# Relay.net
KiCad netlist of a schematic drawn in Altium Designer
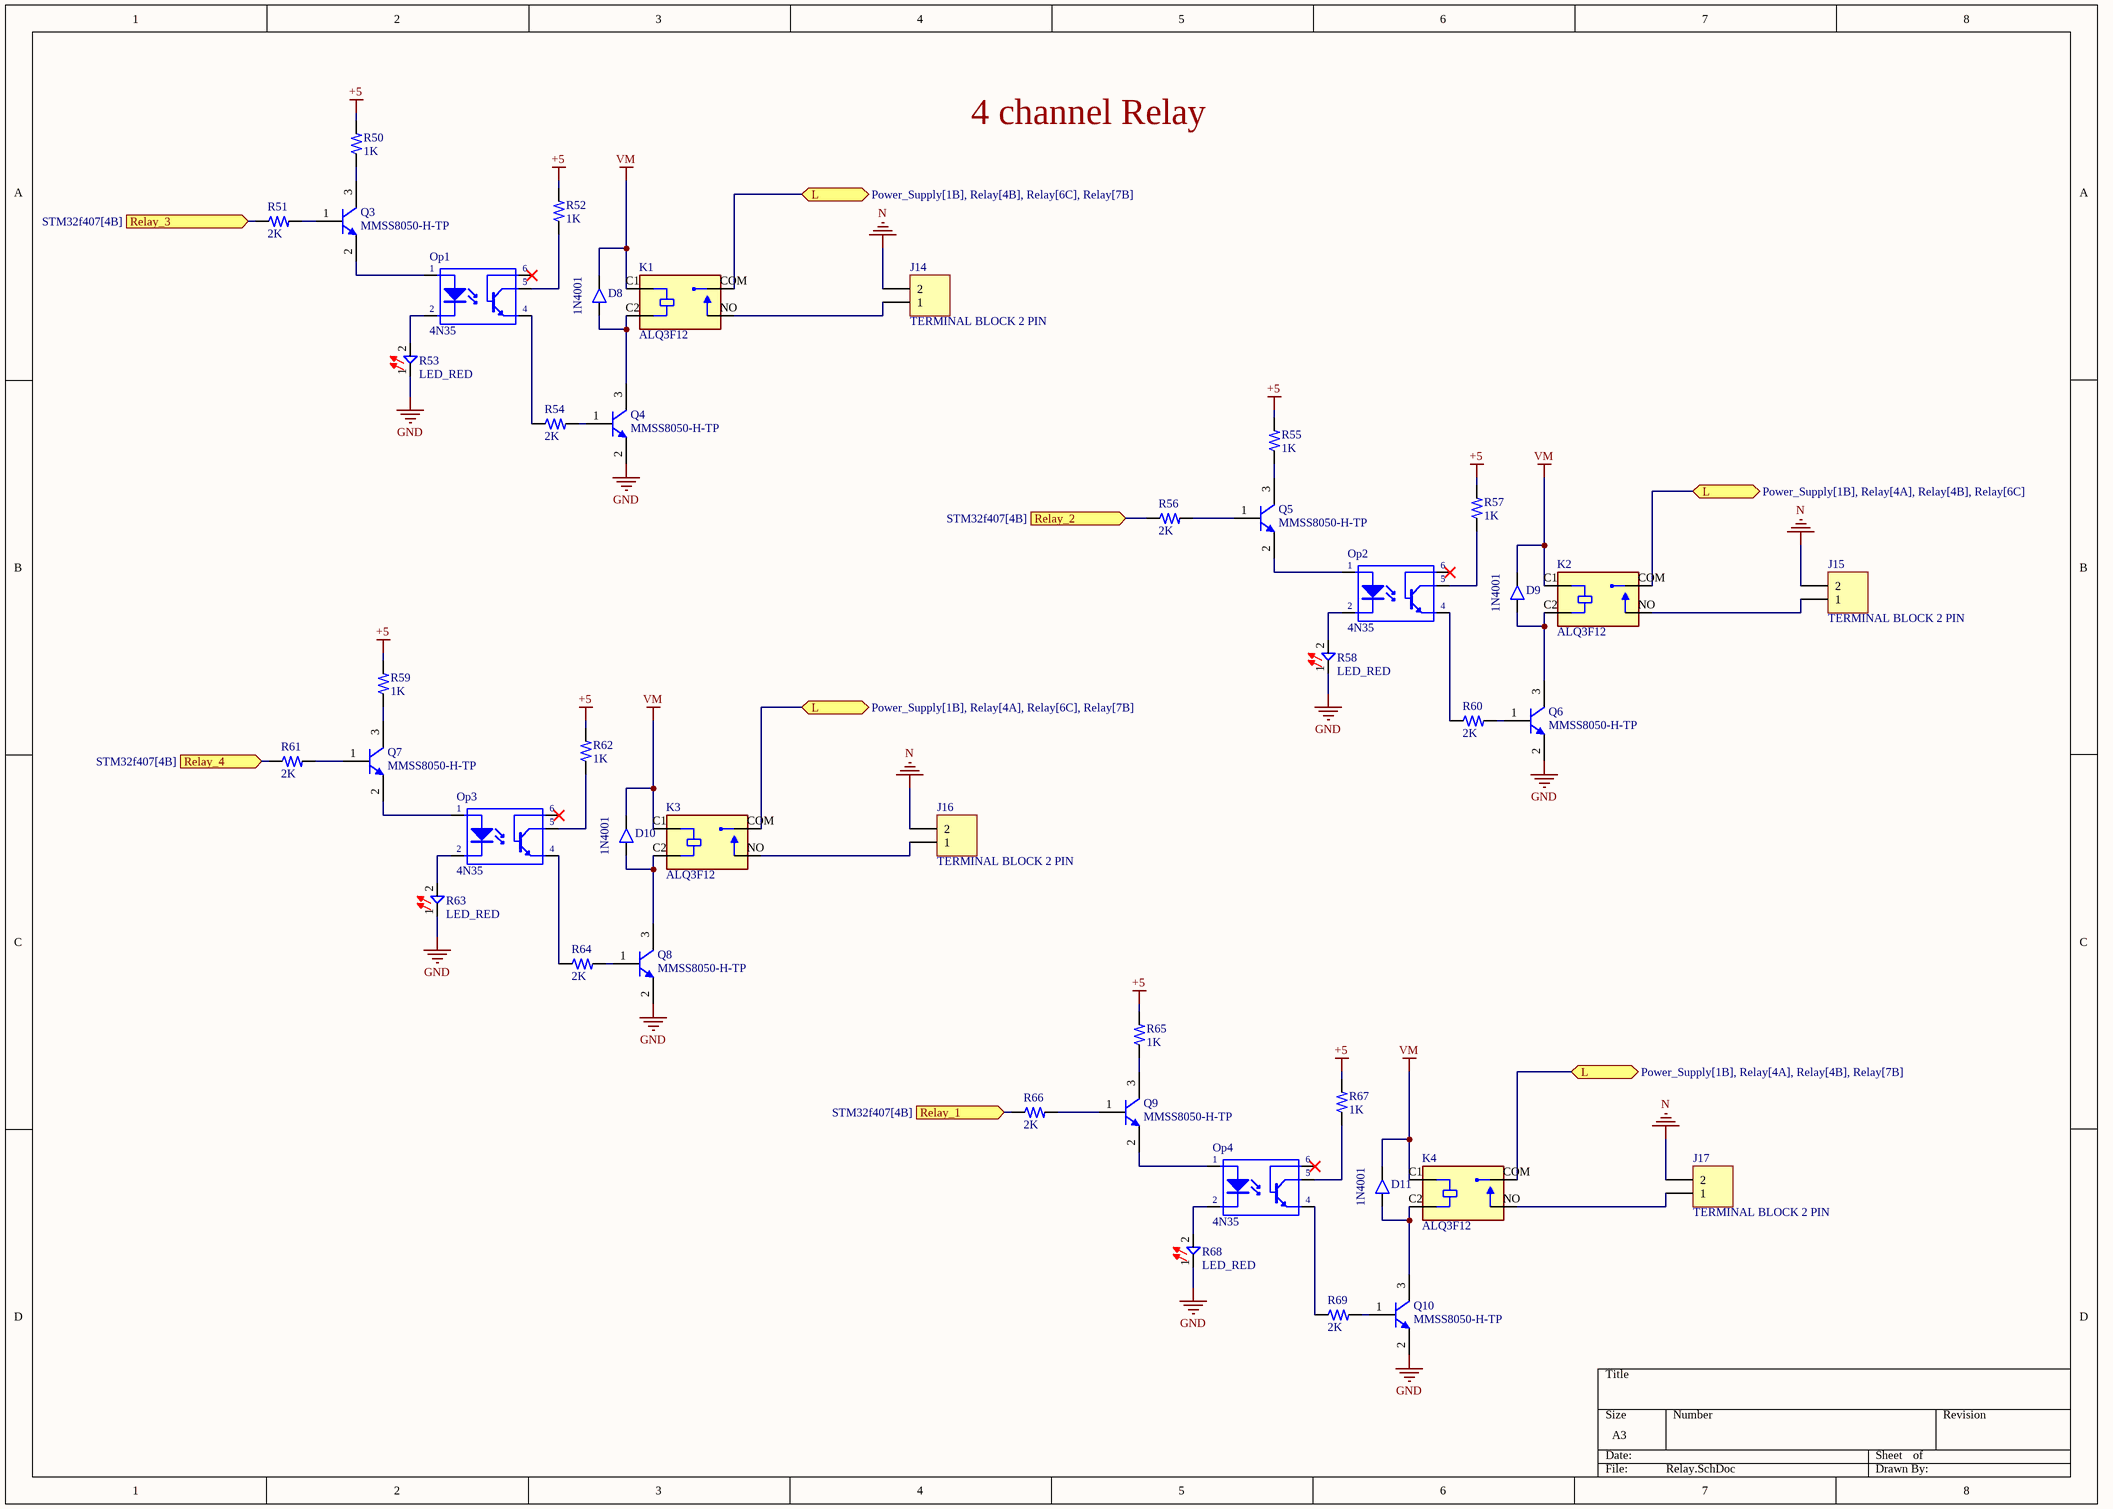
[diagram p0: Relay.SchDoc]

(export (version "E")
  (design (tool "Eeschema 10.0.6"))
  (components
    (comp (ref "D8")
      (value "1N4001")
      (footprint "1N4001")
      (description "1N4001 Series 1 A 50 V Axial Lead Standard Recovery Rectifier - CASE 59-10")
      (fields
        (field (name "MANUFACTURER") "ON Semiconductor")
        (field (name "MANUFACTURER PART NUMBER") "1N4001RLG")
      )
      (libsource (lib "Schematics_Library_Hanif") (part "Diode_1N4001RLG"))
    )
    (comp (ref "D9")
      (value "1N4001")
      (footprint "1N4001")
      (description "1N4001 Series 1 A 50 V Axial Lead Standard Recovery Rectifier - CASE 59-10")
      (fields
        (field (name "MANUFACTURER") "ON Semiconductor")
        (field (name "MANUFACTURER PART NUMBER") "1N4001RLG")
      )
      (libsource (lib "Schematics_Library_Hanif") (part "Diode_1N4001RLG"))
    )
    (comp (ref "D10")
      (value "1N4001")
      (footprint "1N4001")
      (description "1N4001 Series 1 A 50 V Axial Lead Standard Recovery Rectifier - CASE 59-10")
      (fields
        (field (name "MANUFACTURER") "ON Semiconductor")
        (field (name "MANUFACTURER PART NUMBER") "1N4001RLG")
      )
      (libsource (lib "Schematics_Library_Hanif") (part "Diode_1N4001RLG"))
    )
    (comp (ref "D11")
      (value "1N4001")
      (footprint "1N4001")
      (description "1N4001 Series 1 A 50 V Axial Lead Standard Recovery Rectifier - CASE 59-10")
      (fields
        (field (name "MANUFACTURER") "ON Semiconductor")
        (field (name "MANUFACTURER PART NUMBER") "1N4001RLG")
      )
      (libsource (lib "Schematics_Library_Hanif") (part "Diode_1N4001RLG"))
    )
    (comp (ref "J14")
      (value "TERMINAL BLOCK 2 PIN")
      (footprint "CON2_P196_1729128_TH_ST")
      (description "2 Pins, 1 Row 5mm Pitch, straight Connector, male")
      (fields
        (field (name "MANUFACTURER") "Phoenix Contact")
        (field (name "MANUFACTURER PART NUMBER") "MKDSN1,5/2")
      )
      (libsource (lib "Schematics_Library_Hanif") (part "CON-TB_2X1-196-ST-TH"))
    )
    (comp (ref "J15")
      (value "TERMINAL BLOCK 2 PIN")
      (footprint "CON2_P196_1729128_TH_ST")
      (description "2 Pins, 1 Row 5mm Pitch, straight Connector, male")
      (fields
        (field (name "MANUFACTURER") "Phoenix Contact")
        (field (name "MANUFACTURER PART NUMBER") "MKDSN1,5/2")
      )
      (libsource (lib "Schematics_Library_Hanif") (part "CON-TB_2X1-196-ST-TH"))
    )
    (comp (ref "J16")
      (value "TERMINAL BLOCK 2 PIN")
      (footprint "CON2_P196_1729128_TH_ST")
      (description "2 Pins, 1 Row 5mm Pitch, straight Connector, male")
      (fields
        (field (name "MANUFACTURER") "Phoenix Contact")
        (field (name "MANUFACTURER PART NUMBER") "MKDSN1,5/2")
      )
      (libsource (lib "Schematics_Library_Hanif") (part "CON-TB_2X1-196-ST-TH"))
    )
    (comp (ref "J17")
      (value "TERMINAL BLOCK 2 PIN")
      (footprint "CON2_P196_1729128_TH_ST")
      (description "2 Pins, 1 Row 5mm Pitch, straight Connector, male")
      (fields
        (field (name "MANUFACTURER") "Phoenix Contact")
        (field (name "MANUFACTURER PART NUMBER") "MKDSN1,5/2")
      )
      (libsource (lib "Schematics_Library_Hanif") (part "CON-TB_2X1-196-ST-TH"))
    )
    (comp (ref "K1")
      (value "ALQ3F12")
      (footprint "Relay_ALQ3F12")
      (description "RELAY GEN PURPOSE SPST 10A 12V")
      (fields (field (name "MANUFACTURER") "Panasonic"))
      (libsource (lib "Schematics_Library_Hanif") (part "Relay_12V_10A"))
    )
    (comp (ref "K2")
      (value "ALQ3F12")
      (footprint "Relay_ALQ3F12")
      (description "RELAY GEN PURPOSE SPST 10A 12V")
      (fields (field (name "MANUFACTURER") "Panasonic"))
      (libsource (lib "Schematics_Library_Hanif") (part "Relay_12V_10A"))
    )
    (comp (ref "K3")
      (value "ALQ3F12")
      (footprint "Relay_ALQ3F12")
      (description "RELAY GEN PURPOSE SPST 10A 12V")
      (fields (field (name "MANUFACTURER") "Panasonic"))
      (libsource (lib "Schematics_Library_Hanif") (part "Relay_12V_10A"))
    )
    (comp (ref "K4")
      (value "ALQ3F12")
      (footprint "Relay_ALQ3F12")
      (description "RELAY GEN PURPOSE SPST 10A 12V")
      (fields (field (name "MANUFACTURER") "Panasonic"))
      (libsource (lib "Schematics_Library_Hanif") (part "Relay_12V_10A"))
    )
    (comp (ref "Op1")
      (value "4N35")
      (footprint "DIP6_100_300_78X45_TH")
      (description "Power Field-Effect Transistor, 14.5A, 30V, 0.0055ohm, 1-Element, N-Channel, MOSFET")
      (fields
        (field (name "MANUFACTURER") "ON Semiconductor")
        (field (name "MANUFACTURER PART NUMBER") "NTD4804N-35G")
      )
      (libsource (lib "Schematics_Library_Hanif") (part "OPTO_1CH-5KV-50mA-DIP6"))
    )
    (comp (ref "Op2")
      (value "4N35")
      (footprint "DIP6_100_300_78X45_TH")
      (description "Power Field-Effect Transistor, 14.5A, 30V, 0.0055ohm, 1-Element, N-Channel, MOSFET")
      (fields
        (field (name "MANUFACTURER") "ON Semiconductor")
        (field (name "MANUFACTURER PART NUMBER") "NTD4804N-35G")
      )
      (libsource (lib "Schematics_Library_Hanif") (part "OPTO_1CH-5KV-50mA-DIP6"))
    )
    (comp (ref "Op3")
      (value "4N35")
      (footprint "DIP6_100_300_78X45_TH")
      (description "Power Field-Effect Transistor, 14.5A, 30V, 0.0055ohm, 1-Element, N-Channel, MOSFET")
      (fields
        (field (name "MANUFACTURER") "ON Semiconductor")
        (field (name "MANUFACTURER PART NUMBER") "NTD4804N-35G")
      )
      (libsource (lib "Schematics_Library_Hanif") (part "OPTO_1CH-5KV-50mA-DIP6"))
    )
    (comp (ref "Op4")
      (value "4N35")
      (footprint "DIP6_100_300_78X45_TH")
      (description "Power Field-Effect Transistor, 14.5A, 30V, 0.0055ohm, 1-Element, N-Channel, MOSFET")
      (fields
        (field (name "MANUFACTURER") "ON Semiconductor")
        (field (name "MANUFACTURER PART NUMBER") "NTD4804N-35G")
      )
      (libsource (lib "Schematics_Library_Hanif") (part "OPTO_1CH-5KV-50mA-DIP6"))
    )
    (comp (ref "Q3")
      (value "MMSS8050-H-TP")
      (footprint "SOT_23_3")
      (description "Bipolar (BJT) Transistor NPN 25V 1.5A 100MHz 625mW Surface Mount SOT-23")
      (fields (field (name "MANUFACTURER") "MCC"))
      (libsource (lib "Schematics_Library_Hanif") (part "TRNS-NPN_25V-1.5A-SOT23"))
    )
    (comp (ref "Q4")
      (value "MMSS8050-H-TP")
      (footprint "SOT_23_3")
      (description "Bipolar (BJT) Transistor NPN 25V 1.5A 100MHz 625mW Surface Mount SOT-23")
      (fields (field (name "MANUFACTURER") "MCC"))
      (libsource (lib "Schematics_Library_Hanif") (part "TRNS-NPN_25V-1.5A-SOT23"))
    )
    (comp (ref "Q5")
      (value "MMSS8050-H-TP")
      (footprint "SOT_23_3")
      (description "Bipolar (BJT) Transistor NPN 25V 1.5A 100MHz 625mW Surface Mount SOT-23")
      (fields (field (name "MANUFACTURER") "MCC"))
      (libsource (lib "Schematics_Library_Hanif") (part "TRNS-NPN_25V-1.5A-SOT23"))
    )
    (comp (ref "Q6")
      (value "MMSS8050-H-TP")
      (footprint "SOT_23_3")
      (description "Bipolar (BJT) Transistor NPN 25V 1.5A 100MHz 625mW Surface Mount SOT-23")
      (fields (field (name "MANUFACTURER") "MCC"))
      (libsource (lib "Schematics_Library_Hanif") (part "TRNS-NPN_25V-1.5A-SOT23"))
    )
    (comp (ref "Q7")
      (value "MMSS8050-H-TP")
      (footprint "SOT_23_3")
      (description "Bipolar (BJT) Transistor NPN 25V 1.5A 100MHz 625mW Surface Mount SOT-23")
      (fields (field (name "MANUFACTURER") "MCC"))
      (libsource (lib "Schematics_Library_Hanif") (part "TRNS-NPN_25V-1.5A-SOT23"))
    )
    (comp (ref "Q8")
      (value "MMSS8050-H-TP")
      (footprint "SOT_23_3")
      (description "Bipolar (BJT) Transistor NPN 25V 1.5A 100MHz 625mW Surface Mount SOT-23")
      (fields (field (name "MANUFACTURER") "MCC"))
      (libsource (lib "Schematics_Library_Hanif") (part "TRNS-NPN_25V-1.5A-SOT23"))
    )
    (comp (ref "Q9")
      (value "MMSS8050-H-TP")
      (footprint "SOT_23_3")
      (description "Bipolar (BJT) Transistor NPN 25V 1.5A 100MHz 625mW Surface Mount SOT-23")
      (fields (field (name "MANUFACTURER") "MCC"))
      (libsource (lib "Schematics_Library_Hanif") (part "TRNS-NPN_25V-1.5A-SOT23"))
    )
    (comp (ref "Q10")
      (value "MMSS8050-H-TP")
      (footprint "SOT_23_3")
      (description "Bipolar (BJT) Transistor NPN 25V 1.5A 100MHz 625mW Surface Mount SOT-23")
      (fields (field (name "MANUFACTURER") "MCC"))
      (libsource (lib "Schematics_Library_Hanif") (part "TRNS-NPN_25V-1.5A-SOT23"))
    )
    (comp (ref "R50")
      (value "1K")
      (footprint "Resistor_0603")
      (description "Res Thick Film 0603 1K Ohm 1% 0.1W(1/10W) ±100ppm/C Pad SMD T/R")
      (fields
        (field (name "MANUFACTURER") "Walsin Technologies")
        (field (name "MANUFACTURER PART NUMBER") "WR06X1001FTL")
      )
      (libsource (lib "Schematics_Library_Hanif") (part "R_1k_0603"))
    )
    (comp (ref "R51")
      (value "2K")
      (footprint "Resistor_0603")
      (description "Res Thin Film 0603 2K Ohm 1% 0.125W(1/8W) ±100ppm/C Sulfur Resistant Pad SMD T/R")
      (fields
        (field (name "MANUFACTURER") "Stackpole Electronics")
        (field (name "MANUFACTURER PART NUMBER") "RNCP0603FTD2K00")
      )
      (libsource (lib "Schematics_Library_Hanif") (part "R_2k_0603"))
    )
    (comp (ref "R52")
      (value "1K")
      (footprint "Resistor_0603")
      (description "Res Thick Film 0603 1K Ohm 1% 0.1W(1/10W) ±100ppm/C Pad SMD T/R")
      (fields
        (field (name "MANUFACTURER") "Walsin Technologies")
        (field (name "MANUFACTURER PART NUMBER") "WR06X1001FTL")
      )
      (libsource (lib "Schematics_Library_Hanif") (part "R_1k_0603"))
    )
    (comp (ref "R53")
      (value "LED_RED")
      (footprint "LTST-C171KRKT")
      (fields
        (field (name "MANUFACTURER") "Vishay Lite-On")
        (field (name "MANUFACTURER PART NUMBER") "LTST-C171KRKT")
      )
      (libsource (lib "Schematics_Library_Hanif") (part "LED_RED_SMD"))
    )
    (comp (ref "R54")
      (value "2K")
      (footprint "Resistor_0603")
      (description "Res Thin Film 0603 2K Ohm 1% 0.125W(1/8W) ±100ppm/C Sulfur Resistant Pad SMD T/R")
      (fields
        (field (name "MANUFACTURER") "Stackpole Electronics")
        (field (name "MANUFACTURER PART NUMBER") "RNCP0603FTD2K00")
      )
      (libsource (lib "Schematics_Library_Hanif") (part "R_2k_0603"))
    )
    (comp (ref "R55")
      (value "1K")
      (footprint "Resistor_0603")
      (description "Res Thick Film 0603 1K Ohm 1% 0.1W(1/10W) ±100ppm/C Pad SMD T/R")
      (fields
        (field (name "MANUFACTURER") "Walsin Technologies")
        (field (name "MANUFACTURER PART NUMBER") "WR06X1001FTL")
      )
      (libsource (lib "Schematics_Library_Hanif") (part "R_1k_0603"))
    )
    (comp (ref "R56")
      (value "2K")
      (footprint "Resistor_0603")
      (description "Res Thin Film 0603 2K Ohm 1% 0.125W(1/8W) ±100ppm/C Sulfur Resistant Pad SMD T/R")
      (fields
        (field (name "MANUFACTURER") "Stackpole Electronics")
        (field (name "MANUFACTURER PART NUMBER") "RNCP0603FTD2K00")
      )
      (libsource (lib "Schematics_Library_Hanif") (part "R_2k_0603"))
    )
    (comp (ref "R57")
      (value "1K")
      (footprint "Resistor_0603")
      (description "Res Thick Film 0603 1K Ohm 1% 0.1W(1/10W) ±100ppm/C Pad SMD T/R")
      (fields
        (field (name "MANUFACTURER") "Walsin Technologies")
        (field (name "MANUFACTURER PART NUMBER") "WR06X1001FTL")
      )
      (libsource (lib "Schematics_Library_Hanif") (part "R_1k_0603"))
    )
    (comp (ref "R58")
      (value "LED_RED")
      (footprint "LTST-C171KRKT")
      (fields
        (field (name "MANUFACTURER") "Vishay Lite-On")
        (field (name "MANUFACTURER PART NUMBER") "LTST-C171KRKT")
      )
      (libsource (lib "Schematics_Library_Hanif") (part "LED_RED_SMD"))
    )
    (comp (ref "R59")
      (value "1K")
      (footprint "Resistor_0603")
      (description "Res Thick Film 0603 1K Ohm 1% 0.1W(1/10W) ±100ppm/C Pad SMD T/R")
      (fields
        (field (name "MANUFACTURER") "Walsin Technologies")
        (field (name "MANUFACTURER PART NUMBER") "WR06X1001FTL")
      )
      (libsource (lib "Schematics_Library_Hanif") (part "R_1k_0603"))
    )
    (comp (ref "R60")
      (value "2K")
      (footprint "Resistor_0603")
      (description "Res Thin Film 0603 2K Ohm 1% 0.125W(1/8W) ±100ppm/C Sulfur Resistant Pad SMD T/R")
      (fields
        (field (name "MANUFACTURER") "Stackpole Electronics")
        (field (name "MANUFACTURER PART NUMBER") "RNCP0603FTD2K00")
      )
      (libsource (lib "Schematics_Library_Hanif") (part "R_2k_0603"))
    )
    (comp (ref "R61")
      (value "2K")
      (footprint "Resistor_0603")
      (description "Res Thin Film 0603 2K Ohm 1% 0.125W(1/8W) ±100ppm/C Sulfur Resistant Pad SMD T/R")
      (fields
        (field (name "MANUFACTURER") "Stackpole Electronics")
        (field (name "MANUFACTURER PART NUMBER") "RNCP0603FTD2K00")
      )
      (libsource (lib "Schematics_Library_Hanif") (part "R_2k_0603"))
    )
    (comp (ref "R62")
      (value "1K")
      (footprint "Resistor_0603")
      (description "Res Thick Film 0603 1K Ohm 1% 0.1W(1/10W) ±100ppm/C Pad SMD T/R")
      (fields
        (field (name "MANUFACTURER") "Walsin Technologies")
        (field (name "MANUFACTURER PART NUMBER") "WR06X1001FTL")
      )
      (libsource (lib "Schematics_Library_Hanif") (part "R_1k_0603"))
    )
    (comp (ref "R63")
      (value "LED_RED")
      (footprint "LTST-C171KRKT")
      (fields
        (field (name "MANUFACTURER") "Vishay Lite-On")
        (field (name "MANUFACTURER PART NUMBER") "LTST-C171KRKT")
      )
      (libsource (lib "Schematics_Library_Hanif") (part "LED_RED_SMD"))
    )
    (comp (ref "R64")
      (value "2K")
      (footprint "Resistor_0603")
      (description "Res Thin Film 0603 2K Ohm 1% 0.125W(1/8W) ±100ppm/C Sulfur Resistant Pad SMD T/R")
      (fields
        (field (name "MANUFACTURER") "Stackpole Electronics")
        (field (name "MANUFACTURER PART NUMBER") "RNCP0603FTD2K00")
      )
      (libsource (lib "Schematics_Library_Hanif") (part "R_2k_0603"))
    )
    (comp (ref "R65")
      (value "1K")
      (footprint "Resistor_0603")
      (description "Res Thick Film 0603 1K Ohm 1% 0.1W(1/10W) ±100ppm/C Pad SMD T/R")
      (fields
        (field (name "MANUFACTURER") "Walsin Technologies")
        (field (name "MANUFACTURER PART NUMBER") "WR06X1001FTL")
      )
      (libsource (lib "Schematics_Library_Hanif") (part "R_1k_0603"))
    )
    (comp (ref "R66")
      (value "2K")
      (footprint "Resistor_0603")
      (description "Res Thin Film 0603 2K Ohm 1% 0.125W(1/8W) ±100ppm/C Sulfur Resistant Pad SMD T/R")
      (fields
        (field (name "MANUFACTURER") "Stackpole Electronics")
        (field (name "MANUFACTURER PART NUMBER") "RNCP0603FTD2K00")
      )
      (libsource (lib "Schematics_Library_Hanif") (part "R_2k_0603"))
    )
    (comp (ref "R67")
      (value "1K")
      (footprint "Resistor_0603")
      (description "Res Thick Film 0603 1K Ohm 1% 0.1W(1/10W) ±100ppm/C Pad SMD T/R")
      (fields
        (field (name "MANUFACTURER") "Walsin Technologies")
        (field (name "MANUFACTURER PART NUMBER") "WR06X1001FTL")
      )
      (libsource (lib "Schematics_Library_Hanif") (part "R_1k_0603"))
    )
    (comp (ref "R68")
      (value "LED_RED")
      (footprint "LTST-C171KRKT")
      (fields
        (field (name "MANUFACTURER") "Vishay Lite-On")
        (field (name "MANUFACTURER PART NUMBER") "LTST-C171KRKT")
      )
      (libsource (lib "Schematics_Library_Hanif") (part "LED_RED_SMD"))
    )
    (comp (ref "R69")
      (value "2K")
      (footprint "Resistor_0603")
      (description "Res Thin Film 0603 2K Ohm 1% 0.125W(1/8W) ±100ppm/C Sulfur Resistant Pad SMD T/R")
      (fields
        (field (name "MANUFACTURER") "Stackpole Electronics")
        (field (name "MANUFACTURER PART NUMBER") "RNCP0603FTD2K00")
      )
      (libsource (lib "Schematics_Library_Hanif") (part "R_2k_0603"))
    )
  )
  (nets
    (net (code "1") (name "+5") (class "Default")
      (node (ref "R50") (pin "2") (pinfunction "2_2") (pintype "passive"))
      (node (ref "R52") (pin "2") (pinfunction "2_2") (pintype "passive"))
      (node (ref "R55") (pin "2") (pinfunction "2_2") (pintype "passive"))
      (node (ref "R57") (pin "2") (pinfunction "2_2") (pintype "passive"))
      (node (ref "R59") (pin "2") (pinfunction "2_2") (pintype "passive"))
      (node (ref "R62") (pin "2") (pinfunction "2_2") (pintype "passive"))
      (node (ref "R65") (pin "2") (pinfunction "2_2") (pintype "passive"))
      (node (ref "R67") (pin "2") (pinfunction "2_2") (pintype "passive"))
    )
    (net (code "2") (name "/L") (class "Default")
      (node (ref "K1") (pin "COM") (pinfunction "COM_COM") (pintype "passive"))
      (node (ref "K2") (pin "COM") (pinfunction "COM_COM") (pintype "passive"))
      (node (ref "K3") (pin "COM") (pinfunction "COM_COM") (pintype "passive"))
      (node (ref "K4") (pin "COM") (pinfunction "COM_COM") (pintype "passive"))
    )
    (net (code "3") (name "/Relay_1") (class "Default")
      (node (ref "R66") (pin "1") (pinfunction "1_1") (pintype "passive"))
    )
    (net (code "4") (name "/Relay_2") (class "Default")
      (node (ref "R56") (pin "1") (pinfunction "1_1") (pintype "passive"))
    )
    (net (code "5") (name "/Relay_3") (class "Default")
      (node (ref "R51") (pin "1") (pinfunction "1_1") (pintype "passive"))
    )
    (net (code "6") (name "/Relay_4") (class "Default")
      (node (ref "R61") (pin "1") (pinfunction "1_1") (pintype "passive"))
    )
    (net (code "7") (name "GND") (class "Default")
      (node (ref "Q10") (pin "2") (pinfunction "E_2") (pintype "passive"))
      (node (ref "Q4") (pin "2") (pinfunction "E_2") (pintype "passive"))
      (node (ref "Q6") (pin "2") (pinfunction "E_2") (pintype "passive"))
      (node (ref "Q8") (pin "2") (pinfunction "E_2") (pintype "passive"))
      (node (ref "R53") (pin "1") (pinfunction "1_1") (pintype "passive"))
      (node (ref "R58") (pin "1") (pinfunction "1_1") (pintype "passive"))
      (node (ref "R63") (pin "1") (pinfunction "1_1") (pintype "passive"))
      (node (ref "R68") (pin "1") (pinfunction "1_1") (pintype "passive"))
    )
    (net (code "8") (name "N") (class "Default")
      (node (ref "J14") (pin "2") (pinfunction "2_2") (pintype "passive"))
      (node (ref "J15") (pin "2") (pinfunction "2_2") (pintype "passive"))
      (node (ref "J16") (pin "2") (pinfunction "2_2") (pintype "passive"))
      (node (ref "J17") (pin "2") (pinfunction "2_2") (pintype "passive"))
    )
    (net (code "9") (name "Net-(D8-ANODE)") (class "Default")
      (node (ref "D8") (pin "A") (pinfunction "ANODE_A") (pintype "passive"))
      (node (ref "K1") (pin "C2") (pinfunction "COIL2_C2") (pintype "passive"))
      (node (ref "Q4") (pin "3") (pinfunction "C_3") (pintype "passive"))
    )
    (net (code "10") (name "Net-(D9-ANODE)") (class "Default")
      (node (ref "D9") (pin "A") (pinfunction "ANODE_A") (pintype "passive"))
      (node (ref "K2") (pin "C2") (pinfunction "COIL2_C2") (pintype "passive"))
      (node (ref "Q6") (pin "3") (pinfunction "C_3") (pintype "passive"))
    )
    (net (code "11") (name "Net-(D10-ANODE)") (class "Default")
      (node (ref "D10") (pin "A") (pinfunction "ANODE_A") (pintype "passive"))
      (node (ref "K3") (pin "C2") (pinfunction "COIL2_C2") (pintype "passive"))
      (node (ref "Q8") (pin "3") (pinfunction "C_3") (pintype "passive"))
    )
    (net (code "12") (name "Net-(D11-ANODE)") (class "Default")
      (node (ref "D11") (pin "A") (pinfunction "ANODE_A") (pintype "passive"))
      (node (ref "K4") (pin "C2") (pinfunction "COIL2_C2") (pintype "passive"))
      (node (ref "Q10") (pin "3") (pinfunction "C_3") (pintype "passive"))
    )
    (net (code "13") (name "Net-(J14-Pad1)") (class "Default")
      (node (ref "J14") (pin "1") (pinfunction "1_1") (pintype "passive"))
      (node (ref "K1") (pin "NO") (pinfunction "NO_NO") (pintype "passive"))
    )
    (net (code "14") (name "Net-(J15-Pad1)") (class "Default")
      (node (ref "J15") (pin "1") (pinfunction "1_1") (pintype "passive"))
      (node (ref "K2") (pin "NO") (pinfunction "NO_NO") (pintype "passive"))
    )
    (net (code "15") (name "Net-(J16-Pad1)") (class "Default")
      (node (ref "J16") (pin "1") (pinfunction "1_1") (pintype "passive"))
      (node (ref "K3") (pin "NO") (pinfunction "NO_NO") (pintype "passive"))
    )
    (net (code "16") (name "Net-(J17-Pad1)") (class "Default")
      (node (ref "J17") (pin "1") (pinfunction "1_1") (pintype "passive"))
      (node (ref "K4") (pin "NO") (pinfunction "NO_NO") (pintype "passive"))
    )
    (net (code "17") (name "Net-(Op1-A)") (class "Default")
      (node (ref "Op1") (pin "1") (pinfunction "A_1") (pintype "passive"))
      (node (ref "Q3") (pin "2") (pinfunction "E_2") (pintype "passive"))
    )
    (net (code "18") (name "Net-(Op1-C-Pad5)") (class "Default")
      (node (ref "Op1") (pin "5") (pinfunction "C_5") (pintype "passive"))
      (node (ref "R52") (pin "1") (pinfunction "1_1") (pintype "passive"))
    )
    (net (code "19") (name "Net-(Op1-E)") (class "Default")
      (node (ref "Op1") (pin "4") (pinfunction "E_4") (pintype "passive"))
      (node (ref "R54") (pin "1") (pinfunction "1_1") (pintype "passive"))
    )
    (net (code "20") (name "Net-(Op1-K)") (class "Default")
      (node (ref "Op1") (pin "2") (pinfunction "K_2") (pintype "passive"))
      (node (ref "R53") (pin "2") (pinfunction "2_2") (pintype "passive"))
    )
    (net (code "21") (name "Net-(Op2-A)") (class "Default")
      (node (ref "Op2") (pin "1") (pinfunction "A_1") (pintype "passive"))
      (node (ref "Q5") (pin "2") (pinfunction "E_2") (pintype "passive"))
    )
    (net (code "22") (name "Net-(Op2-C-Pad5)") (class "Default")
      (node (ref "Op2") (pin "5") (pinfunction "C_5") (pintype "passive"))
      (node (ref "R57") (pin "1") (pinfunction "1_1") (pintype "passive"))
    )
    (net (code "23") (name "Net-(Op2-E)") (class "Default")
      (node (ref "Op2") (pin "4") (pinfunction "E_4") (pintype "passive"))
      (node (ref "R60") (pin "1") (pinfunction "1_1") (pintype "passive"))
    )
    (net (code "24") (name "Net-(Op2-K)") (class "Default")
      (node (ref "Op2") (pin "2") (pinfunction "K_2") (pintype "passive"))
      (node (ref "R58") (pin "2") (pinfunction "2_2") (pintype "passive"))
    )
    (net (code "25") (name "Net-(Op3-A)") (class "Default")
      (node (ref "Op3") (pin "1") (pinfunction "A_1") (pintype "passive"))
      (node (ref "Q7") (pin "2") (pinfunction "E_2") (pintype "passive"))
    )
    (net (code "26") (name "Net-(Op3-C-Pad5)") (class "Default")
      (node (ref "Op3") (pin "5") (pinfunction "C_5") (pintype "passive"))
      (node (ref "R62") (pin "1") (pinfunction "1_1") (pintype "passive"))
    )
    (net (code "27") (name "Net-(Op3-E)") (class "Default")
      (node (ref "Op3") (pin "4") (pinfunction "E_4") (pintype "passive"))
      (node (ref "R64") (pin "1") (pinfunction "1_1") (pintype "passive"))
    )
    (net (code "28") (name "Net-(Op3-K)") (class "Default")
      (node (ref "Op3") (pin "2") (pinfunction "K_2") (pintype "passive"))
      (node (ref "R63") (pin "2") (pinfunction "2_2") (pintype "passive"))
    )
    (net (code "29") (name "Net-(Op4-A)") (class "Default")
      (node (ref "Op4") (pin "1") (pinfunction "A_1") (pintype "passive"))
      (node (ref "Q9") (pin "2") (pinfunction "E_2") (pintype "passive"))
    )
    (net (code "30") (name "Net-(Op4-C-Pad5)") (class "Default")
      (node (ref "Op4") (pin "5") (pinfunction "C_5") (pintype "passive"))
      (node (ref "R67") (pin "1") (pinfunction "1_1") (pintype "passive"))
    )
    (net (code "31") (name "Net-(Op4-E)") (class "Default")
      (node (ref "Op4") (pin "4") (pinfunction "E_4") (pintype "passive"))
      (node (ref "R69") (pin "1") (pinfunction "1_1") (pintype "passive"))
    )
    (net (code "32") (name "Net-(Op4-K)") (class "Default")
      (node (ref "Op4") (pin "2") (pinfunction "K_2") (pintype "passive"))
      (node (ref "R68") (pin "2") (pinfunction "2_2") (pintype "passive"))
    )
    (net (code "33") (name "Net-(Q3-B)") (class "Default")
      (node (ref "Q3") (pin "1") (pinfunction "B_1") (pintype "passive"))
      (node (ref "R51") (pin "2") (pinfunction "2_2") (pintype "passive"))
    )
    (net (code "34") (name "Net-(Q3-C)") (class "Default")
      (node (ref "Q3") (pin "3") (pinfunction "C_3") (pintype "passive"))
      (node (ref "R50") (pin "1") (pinfunction "1_1") (pintype "passive"))
    )
    (net (code "35") (name "Net-(Q4-B)") (class "Default")
      (node (ref "Q4") (pin "1") (pinfunction "B_1") (pintype "passive"))
      (node (ref "R54") (pin "2") (pinfunction "2_2") (pintype "passive"))
    )
    (net (code "36") (name "Net-(Q5-B)") (class "Default")
      (node (ref "Q5") (pin "1") (pinfunction "B_1") (pintype "passive"))
      (node (ref "R56") (pin "2") (pinfunction "2_2") (pintype "passive"))
    )
    (net (code "37") (name "Net-(Q5-C)") (class "Default")
      (node (ref "Q5") (pin "3") (pinfunction "C_3") (pintype "passive"))
      (node (ref "R55") (pin "1") (pinfunction "1_1") (pintype "passive"))
    )
    (net (code "38") (name "Net-(Q6-B)") (class "Default")
      (node (ref "Q6") (pin "1") (pinfunction "B_1") (pintype "passive"))
      (node (ref "R60") (pin "2") (pinfunction "2_2") (pintype "passive"))
    )
    (net (code "39") (name "Net-(Q7-B)") (class "Default")
      (node (ref "Q7") (pin "1") (pinfunction "B_1") (pintype "passive"))
      (node (ref "R61") (pin "2") (pinfunction "2_2") (pintype "passive"))
    )
    (net (code "40") (name "Net-(Q7-C)") (class "Default")
      (node (ref "Q7") (pin "3") (pinfunction "C_3") (pintype "passive"))
      (node (ref "R59") (pin "1") (pinfunction "1_1") (pintype "passive"))
    )
    (net (code "41") (name "Net-(Q8-B)") (class "Default")
      (node (ref "Q8") (pin "1") (pinfunction "B_1") (pintype "passive"))
      (node (ref "R64") (pin "2") (pinfunction "2_2") (pintype "passive"))
    )
    (net (code "42") (name "Net-(Q9-B)") (class "Default")
      (node (ref "Q9") (pin "1") (pinfunction "B_1") (pintype "passive"))
      (node (ref "R66") (pin "2") (pinfunction "2_2") (pintype "passive"))
    )
    (net (code "43") (name "Net-(Q9-C)") (class "Default")
      (node (ref "Q9") (pin "3") (pinfunction "C_3") (pintype "passive"))
      (node (ref "R65") (pin "1") (pinfunction "1_1") (pintype "passive"))
    )
    (net (code "44") (name "Net-(Q10-B)") (class "Default")
      (node (ref "Q10") (pin "1") (pinfunction "B_1") (pintype "passive"))
      (node (ref "R69") (pin "2") (pinfunction "2_2") (pintype "passive"))
    )
    (net (code "45") (name "VM") (class "Default")
      (node (ref "D10") (pin "C") (pinfunction "CATHODE_C") (pintype "passive"))
      (node (ref "D11") (pin "C") (pinfunction "CATHODE_C") (pintype "passive"))
      (node (ref "D8") (pin "C") (pinfunction "CATHODE_C") (pintype "passive"))
      (node (ref "D9") (pin "C") (pinfunction "CATHODE_C") (pintype "passive"))
      (node (ref "K1") (pin "C1") (pinfunction "COIL1_C1") (pintype "passive"))
      (node (ref "K2") (pin "C1") (pinfunction "COIL1_C1") (pintype "passive"))
      (node (ref "K3") (pin "C1") (pinfunction "COIL1_C1") (pintype "passive"))
      (node (ref "K4") (pin "C1") (pinfunction "COIL1_C1") (pintype "passive"))
    )
    (net (code "46") (name "unconnected-(Op1-C-Pad6)") (class "Default")
      (node (ref "Op1") (pin "6") (pinfunction "C_6") (pintype "passive+no_connect"))
    )
    (net (code "47") (name "unconnected-(Op2-C-Pad6)") (class "Default")
      (node (ref "Op2") (pin "6") (pinfunction "C_6") (pintype "passive+no_connect"))
    )
    (net (code "48") (name "unconnected-(Op3-C-Pad6)") (class "Default")
      (node (ref "Op3") (pin "6") (pinfunction "C_6") (pintype "passive+no_connect"))
    )
    (net (code "49") (name "unconnected-(Op4-C-Pad6)") (class "Default")
      (node (ref "Op4") (pin "6") (pinfunction "C_6") (pintype "passive+no_connect"))
    )
  )
)
